# Power_Stage.net
KiCad netlist of a schematic drawn in Altium Designer
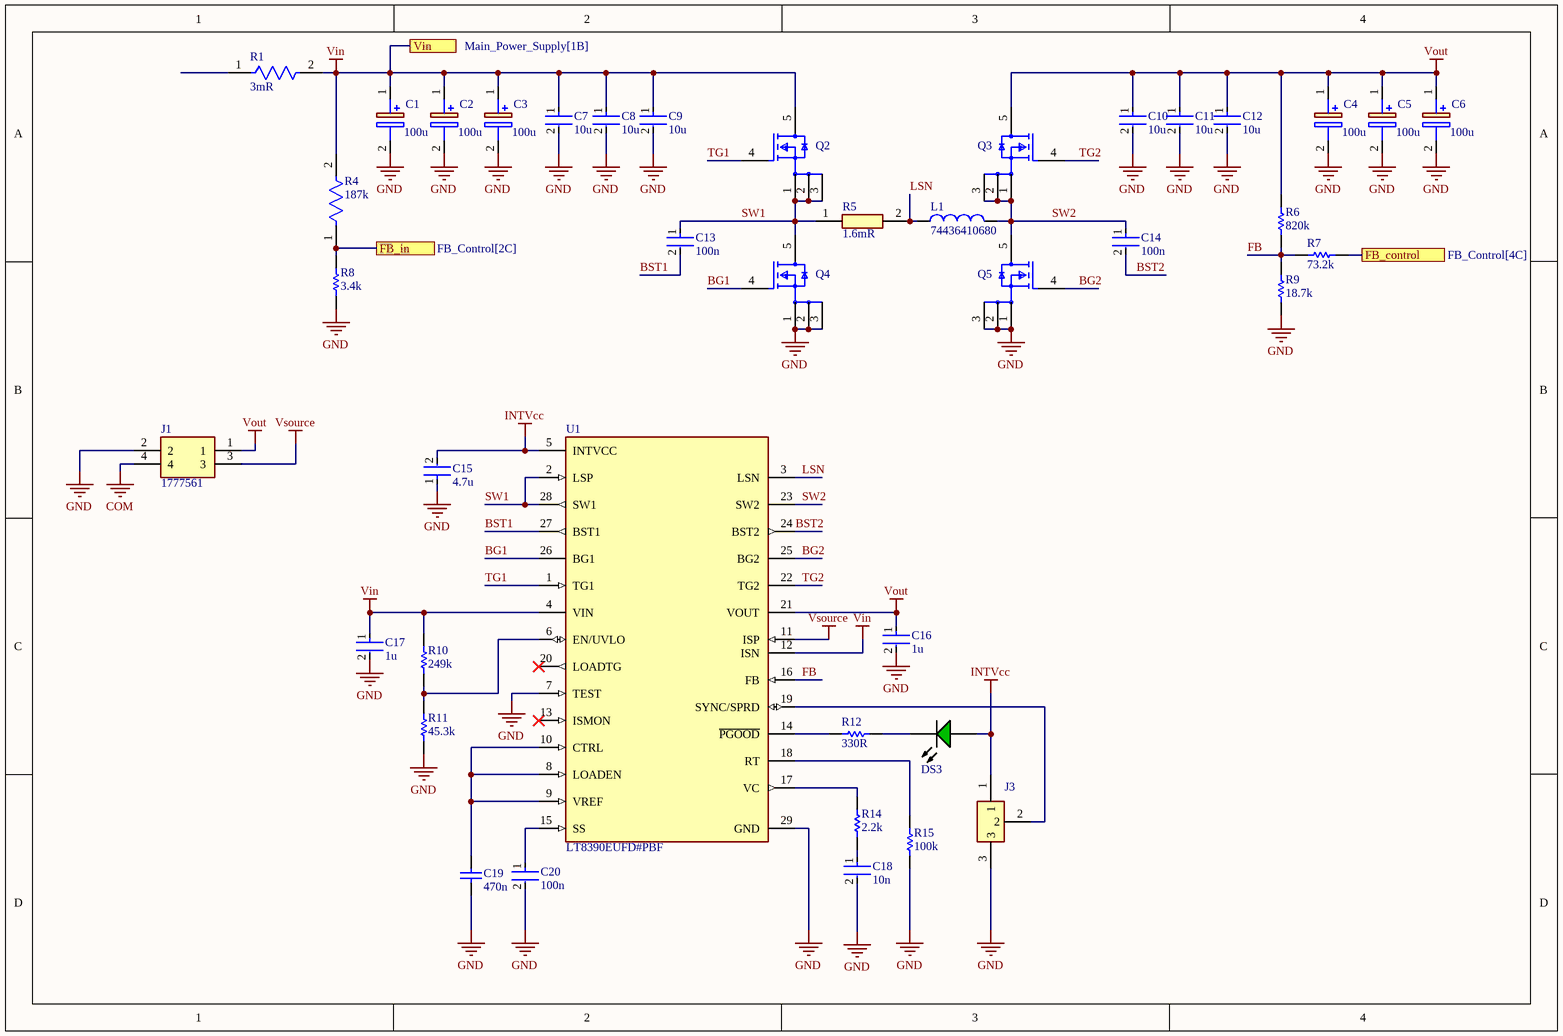
[diagram p0: Power_Stage.SchDoc]

(export (version "E")
  (design (tool "Eeschema 10.0.6"))
  (components
    (comp (ref "C1")
      (value "100u")
      (footprint "Library:CAPPRD500W65D1025H1700")
      (description "Aluminium Electrolytic Capacitors 100uF 100V - Radial Leaded Al Lytic Cap 85C Radial M Series")
      (fields
        (field (name "MANUFACTURER_PART_NUMBER") "ECA-2AM101B")
        (field (name "MOUSER PART NUMBER") "667-ECA-2AM101B")
      )
      (libsource (lib "*") (part "ECA-2AM101B"))
    )
    (comp (ref "C2")
      (value "100u")
      (footprint "Library:CAPPRD500W65D1025H1700")
      (description "Aluminium Electrolytic Capacitors 100uF 100V - Radial Leaded Al Lytic Cap 85C Radial M Series")
      (fields
        (field (name "MANUFACTURER_PART_NUMBER") "ECA-2AM101B")
        (field (name "MOUSER PART NUMBER") "667-ECA-2AM101B")
      )
      (libsource (lib "*") (part "ECA-2AM101B"))
    )
    (comp (ref "C3")
      (value "100u")
      (footprint "Library:CAPPRD500W65D1025H1700")
      (description "Aluminium Electrolytic Capacitors 100uF 100V - Radial Leaded Al Lytic Cap 85C Radial M Series")
      (fields
        (field (name "MANUFACTURER_PART_NUMBER") "ECA-2AM101B")
        (field (name "MOUSER PART NUMBER") "667-ECA-2AM101B")
      )
      (libsource (lib "*") (part "ECA-2AM101B"))
    )
    (comp (ref "C4")
      (value "100u")
      (footprint "Library:CAPPRD500W65D1025H1700")
      (description "Aluminium Electrolytic Capacitors 100uF 100V - Radial Leaded Al Lytic Cap 85C Radial M Series")
      (fields
        (field (name "MANUFACTURER_PART_NUMBER") "ECA-2AM101B")
        (field (name "MOUSER PART NUMBER") "667-ECA-2AM101B")
      )
      (libsource (lib "*") (part "ECA-2AM101B"))
    )
    (comp (ref "C5")
      (value "100u")
      (footprint "Library:CAPPRD500W65D1025H1700")
      (description "Aluminium Electrolytic Capacitors 100uF 100V - Radial Leaded Al Lytic Cap 85C Radial M Series")
      (fields
        (field (name "MANUFACTURER_PART_NUMBER") "ECA-2AM101B")
        (field (name "MOUSER PART NUMBER") "667-ECA-2AM101B")
      )
      (libsource (lib "*") (part "ECA-2AM101B"))
    )
    (comp (ref "C6")
      (value "100u")
      (footprint "Library:CAPPRD500W65D1025H1700")
      (description "Aluminium Electrolytic Capacitors 100uF 100V - Radial Leaded Al Lytic Cap 85C Radial M Series")
      (fields
        (field (name "MANUFACTURER_PART_NUMBER") "ECA-2AM101B")
        (field (name "MOUSER PART NUMBER") "667-ECA-2AM101B")
      )
      (libsource (lib "*") (part "ECA-2AM101B"))
    )
    (comp (ref "C7")
      (value "10u")
      (footprint "FP-GRM32E-0_3-0_2-MFG")
      (description "Chip Multilayer Ceramic Capacitors for General Purpose, 1210, 10uF, X7S, 22%, 10%, 100V")
      (fields (field (name "TOLERANCE") "10%"))
      (libsource (lib "Altium Content Vault") (part "02cd4be3c70576c341d710602a673aa"))
    )
    (comp (ref "C8")
      (value "10u")
      (footprint "FP-GRM32E-0_3-0_2-MFG")
      (description "Chip Multilayer Ceramic Capacitors for General Purpose, 1210, 10uF, X7S, 22%, 10%, 100V")
      (fields (field (name "TOLERANCE") "10%"))
      (libsource (lib "Altium Content Vault") (part "02cd4be3c70576c341d710602a673aa"))
    )
    (comp (ref "C9")
      (value "10u")
      (footprint "FP-GRM32E-0_3-0_2-MFG")
      (description "Chip Multilayer Ceramic Capacitors for General Purpose, 1210, 10uF, X7S, 22%, 10%, 100V")
      (fields (field (name "TOLERANCE") "10%"))
      (libsource (lib "Altium Content Vault") (part "02cd4be3c70576c341d710602a673aa"))
    )
    (comp (ref "C10")
      (value "10u")
      (footprint "FP-GRM32E-0_3-0_2-MFG")
      (description "Chip Multilayer Ceramic Capacitors for General Purpose, 1210, 10uF, X7S, 22%, 10%, 100V")
      (fields (field (name "TOLERANCE") "10%"))
      (libsource (lib "Altium Content Vault") (part "02cd4be3c70576c341d710602a673aa"))
    )
    (comp (ref "C11")
      (value "10u")
      (footprint "FP-GRM32E-0_3-0_2-MFG")
      (description "Chip Multilayer Ceramic Capacitors for General Purpose, 1210, 10uF, X7S, 22%, 10%, 100V")
      (fields (field (name "TOLERANCE") "10%"))
      (libsource (lib "Altium Content Vault") (part "02cd4be3c70576c341d710602a673aa"))
    )
    (comp (ref "C12")
      (value "10u")
      (footprint "FP-GRM32E-0_3-0_2-MFG")
      (description "Chip Multilayer Ceramic Capacitors for General Purpose, 1210, 10uF, X7S, 22%, 10%, 100V")
      (fields (field (name "TOLERANCE") "10%"))
      (libsource (lib "Altium Content Vault") (part "02cd4be3c70576c341d710602a673aa"))
    )
    (comp (ref "C13")
      (value "100n")
      (footprint "FP-0805-L_2_01_0_2-W_1_25-MFG")
      (description "General Purpose Ceramic Capacitor, 0805, 100nF, 5%, X7R, 0.15, 50V")
      (fields (field (name "TOLERANCE") "5%") (field (name "VOLTAGE") "50V"))
      (libsource (lib "Altium Content Vault") (part "02cd4be3c70576c341d710602a673aa"))
    )
    (comp (ref "C14")
      (value "100n")
      (footprint "FP-0805-L_2_01_0_2-W_1_25-MFG")
      (description "General Purpose Ceramic Capacitor, 0805, 100nF, 5%, X7R, 0.15, 50V")
      (fields (field (name "TOLERANCE") "5%") (field (name "VOLTAGE") "50V"))
      (libsource (lib "Altium Content Vault") (part "02cd4be3c70576c341d710602a673aa"))
    )
    (comp (ref "C15")
      (value "4.7u")
      (footprint "FP-0805-L_2_01_0_2-W_1_25-IPC_A")
      (description "General Purpose Ceramic Capacitor, 0805, 4.7uF, 10%, X5R, 0.15, 10V")
      (fields (field (name "VOLTAGE") "10V") (field (name "TOLERANCE") "10%"))
      (libsource (lib "Altium Content Vault") (part "02cd4be3c70576c341d710602a673aa"))
    )
    (comp (ref "C16")
      (value "1u")
      (footprint "FP-1210-L_3_3_0_4-W_2_5_0-IPC_C")
      (description "General Purpose Ceramic Capacitor, 1210, 1uF, 10%, X7R, 15%, 100V")
      (fields (field (name "TOLERANCE") "20%") (field (name "VOLTAGE") "100V"))
      (libsource (lib "Altium Content Vault") (part "b4654b650e69147ec39a6b967a45e02"))
    )
    (comp (ref "C17")
      (value "1u")
      (footprint "FP-1210-L_3_3_0_4-W_2_5_0-IPC_C")
      (description "General Purpose Ceramic Capacitor, 1210, 1uF, 10%, X7R, 15%, 100V")
      (fields (field (name "TOLERANCE") "20%") (field (name "VOLTAGE") "100V"))
      (libsource (lib "Altium Content Vault") (part "b4654b650e69147ec39a6b967a45e02"))
    )
    (comp (ref "C18")
      (value "10n")
      (footprint "FP-0805-L_2_01_0_2-W_1_25-IPC_B")
      (description "General Purpose Ceramic Capacitor, 0805, 10nF, 5%, X7R, 0.15, 50V")
      (fields (field (name "VOLTAGE") "50V") (field (name "TOLERANCE") "5%"))
      (libsource (lib "Altium Content Vault") (part "02cd4be3c70576c341d710602a673aa"))
    )
    (comp (ref "C19")
      (value "470n")
      (footprint "CAPC2013X140X50ML20T25")
      (fields
        (field (name "MANUFACTURER") "AVX Interconnect / Elco")
        (field (name "PART NUMBER") "08055C474JAT2A")
      )
      (libsource (lib "Altium Content Vault") (part "CAP"))
    )
    (comp (ref "C20")
      (value "100n")
      (footprint "FP-0805-L_2_01_0_2-W_1_25-MFG")
      (description "General Purpose Ceramic Capacitor, 0805, 100nF, 5%, X7R, 0.15, 50V")
      (fields (field (name "TOLERANCE") "5%") (field (name "VOLTAGE") "50V"))
      (libsource (lib "Altium Content Vault") (part "02cd4be3c70576c341d710602a673aa"))
    )
    (comp (ref "DS3")
      (value "LTST-C170KGKT")
      (footprint "LTST-LTST-C170KGKT-2_V")
      (description "Ultra Bright AlInGaP Chip LED, 75 mW, -55 to 85 degC, 2-Pin SMD (0805), RoHS, Tape and Reel")
      (fields (field (name "MANUFACTURER") "Lite-On"))
      (libsource (lib "Altium Content Vault") (part "LED-GREEN-KA-2"))
    )
    (comp (ref "J1")
      (value "1777561")
      (footprint "Library:1777561")
      (description "Connector")
      (fields (field (name "MOUSER PART NUMBER") "651-1777561"))
      (libsource (lib "Library") (part "1777561"))
    )
    (comp (ref "J3")
      (value "22-28-4030")
      (footprint "Library:MOLEX_22-28-4030")
      (description "Connector Header Through Hole 3 position 0.100\" (2.54mm)")
      (libsource (lib "Library") (part "22-28-4030"))
    )
    (comp (ref "L1")
      (value "74436410680")
      (footprint "WE-HCF_2815")
      (description "74436410680 Inductor, high current, 6.8uH, 1.44mOhm, 27mmL x 28mmW x 15.4mmH, SMT")
      (libsource (lib "Altium Content Vault") (part "Inductor - 1"))
    )
    (comp (ref "Q2")
      (value "NVMYS3D3N06CLTWG")
      (footprint "FP-760AB-MFG")
      (description "NVMYS3D3N06CLTWG Single Mosfet Transistors Rohs Compliant: Yes")
      (libsource (lib "Altium Content Vault") (part "47be8b74c5e268e5f463571878acc0e"))
    )
    (comp (ref "Q3")
      (value "NVMYS3D3N06CLTWG")
      (footprint "FP-760AB-MFG")
      (description "NVMYS3D3N06CLTWG Single Mosfet Transistors Rohs Compliant: Yes")
      (libsource (lib "Altium Content Vault") (part "47be8b74c5e268e5f463571878acc0e"))
    )
    (comp (ref "Q4")
      (value "NVMYS3D3N06CLTWG")
      (footprint "FP-760AB-MFG")
      (description "NVMYS3D3N06CLTWG Single Mosfet Transistors Rohs Compliant: Yes")
      (libsource (lib "Altium Content Vault") (part "47be8b74c5e268e5f463571878acc0e"))
    )
    (comp (ref "Q5")
      (value "NVMYS3D3N06CLTWG")
      (footprint "FP-760AB-MFG")
      (description "NVMYS3D3N06CLTWG Single Mosfet Transistors Rohs Compliant: Yes")
      (libsource (lib "Altium Content Vault") (part "47be8b74c5e268e5f463571878acc0e"))
    )
    (comp (ref "R1")
      (value "3mR")
      (footprint "FP-CSS2H-3920K-3L00FE-MFG")
      (description "RES 0.003 OHM 1% 5W 3920")
      (fields (field (name "TOLERANCE") "1%"))
      (libsource (lib "Altium Content Vault") (part "1029c3af85768c4190bb7ad29bc67b5"))
    )
    (comp (ref "R4")
      (value "187k")
      (footprint "FP-ERJ3EK-MFG")
      (description "RES SMD 187K OHM 1% 1/10W 0603")
      (fields (field (name "TOLERANCE") "1%"))
      (libsource (lib "Altium Content Vault") (part "1029c3af85768c4190bb7ad29bc67b5"))
    )
    (comp (ref "R5")
      (value "1.6mR")
      (footprint "Library:RESC6432X89N")
      (description "Current Sense Resistors - SMD 3watt .0016ohm 1%")
      (fields (field (name "MANUFACTURER_PART_NUMBER") "WSLP25121L600FEA"))
      (libsource (lib "*") (part "WSLP25121L600FEA"))
    )
    (comp (ref "R6")
      (value "820k")
      (footprint "RESC1608X55X30ML15T15")
      (fields (field (name "MANUFACTURER") "Panasonic") (field (name "PART NUMBER") "ERJ3EKF8203V"))
      (libsource (lib "Altium Content Vault") (part "RES"))
    )
    (comp (ref "R7")
      (value "73.2k")
      (footprint "RESC1005X40X25LL05T05")
      (fields (field (name "PART NUMBER") "ERJ-2RKF7322X") (field (name "MANUFACTURER") "Panasonic"))
      (libsource (lib "Altium Content Vault") (part "RES"))
    )
    (comp (ref "R8")
      (value "3.4k")
      (footprint "RESC1608X55X30LL15T15")
      (fields (field (name "PART NUMBER") "ERJ-3EKF3401V") (field (name "MANUFACTURER") "Panasonic"))
      (libsource (lib "Altium Content Vault") (part "RES"))
    )
    (comp (ref "R9")
      (value "18.7k")
      (footprint "RESC1608X55X30LL15T15")
      (fields (field (name "PART NUMBER") "ERJ-3EKF1872V") (field (name "MANUFACTURER") "Panasonic"))
      (libsource (lib "Altium Content Vault") (part "RES"))
    )
    (comp (ref "R10")
      (value "249k")
      (footprint "RESC1608X55X30ML15T15")
      (fields (field (name "PART NUMBER") "ERJ-3EKF2493V") (field (name "MANUFACTURER") "Panasonic"))
      (libsource (lib "Altium Content Vault") (part "RES"))
    )
    (comp (ref "R11")
      (value "45.3k")
      (footprint "RESC1608X55X30ML15T15")
      (fields (field (name "MANUFACTURER") "Panasonic") (field (name "PART NUMBER") "ERJ-3EKF4532V"))
      (libsource (lib "Altium Content Vault") (part "RES"))
    )
    (comp (ref "R12")
      (value "330R")
      (footprint "RESC1608X55X30LL15T15")
      (description "Chip Resistor, 330 Ohm, +/- 1%, 0.1 W, -55 to 155 degC, 0603 (1608 Metric), RoHS, Tape and Reel")
      (libsource (lib "Altium Content Vault") (part "RES-2"))
    )
    (comp (ref "R14")
      (value "2.2k")
      (footprint "RESC1608X55X30LL15T15")
      (fields (field (name "PART NUMBER") "ERJ3EKF2201V") (field (name "MANUFACTURER") "Panasonic"))
      (libsource (lib "Altium Content Vault") (part "RES"))
    )
    (comp (ref "R15")
      (value "100k")
      (footprint "RESC1608X55X30ML15T15")
      (fields (field (name "PART NUMBER") "ERJ-3EKF1003V") (field (name "MANUFACTURER") "Panasonic"))
      (libsource (lib "Altium Content Vault") (part "RES"))
    )
    (comp (ref "U1")
      (value "LT8390EUFD#PBF")
      (footprint "FP-UFD-28-05-08-1712-MFG")
      (description "IC REG CTRLR BUCK/BOOST 28QFN")
      (libsource (lib "Altium Content Vault") (part "bdcd0505c8727e03998dc9dfa31625b"))
    )
  )
  (nets
    (net (code "1") (name "/BG1") (class "Default")
      (node (ref "Q4") (pin "4") (pinfunction "G_4") (pintype "passive"))
      (node (ref "U1") (pin "26") (pinfunction "BG1_26") (pintype "passive"))
    )
    (net (code "2") (name "/BG2") (class "Default")
      (node (ref "Q5") (pin "4") (pinfunction "G_4") (pintype "passive"))
      (node (ref "U1") (pin "25") (pinfunction "BG2_25") (pintype "passive"))
    )
    (net (code "3") (name "/BST1") (class "Default")
      (node (ref "C13") (pin "2") (pinfunction "2_2") (pintype "passive"))
      (node (ref "U1") (pin "27") (pinfunction "BST1_27") (pintype "output"))
    )
    (net (code "4") (name "/BST2") (class "Default")
      (node (ref "C14") (pin "2") (pinfunction "2_2") (pintype "passive"))
      (node (ref "U1") (pin "24") (pinfunction "BST2_24") (pintype "output"))
    )
    (net (code "5") (name "/FB") (class "Default")
      (node (ref "R6") (pin "1") (pinfunction "1_1") (pintype "passive"))
      (node (ref "R7") (pin "1") (pinfunction "1_1") (pintype "passive"))
      (node (ref "R9") (pin "2") (pinfunction "2_2") (pintype "passive"))
      (node (ref "U1") (pin "16") (pinfunction "FB_16") (pintype "input"))
    )
    (net (code "6") (name "/FB_control") (class "Default")
      (node (ref "R7") (pin "2") (pinfunction "2_2") (pintype "passive"))
    )
    (net (code "7") (name "/FB_in") (class "Default")
      (node (ref "R4") (pin "1") (pinfunction "1_1") (pintype "passive"))
      (node (ref "R8") (pin "2") (pinfunction "2_2") (pintype "passive"))
    )
    (net (code "8") (name "/LSN") (class "Default")
      (node (ref "L1") (pin "1") (pinfunction "1_1") (pintype "passive"))
      (node (ref "R5") (pin "2") (pinfunction "2_2") (pintype "passive"))
      (node (ref "U1") (pin "3") (pinfunction "LSN_3") (pintype "power_in"))
    )
    (net (code "9") (name "/SW1") (class "Default")
      (node (ref "C13") (pin "1") (pinfunction "1_1") (pintype "passive"))
      (node (ref "Q2") (pin "1") (pinfunction "S_1") (pintype "passive"))
      (node (ref "Q2") (pin "2") (pinfunction "S_2") (pintype "passive"))
      (node (ref "Q2") (pin "3") (pinfunction "S_3") (pintype "passive"))
      (node (ref "Q4") (pin "5") (pinfunction "D_5") (pintype "passive"))
      (node (ref "R5") (pin "1") (pinfunction "1_1") (pintype "passive"))
      (node (ref "U1") (pin "2") (pinfunction "LSP_2") (pintype "input"))
      (node (ref "U1") (pin "28") (pinfunction "SW1_28") (pintype "output"))
    )
    (net (code "10") (name "/SW2") (class "Default")
      (node (ref "C14") (pin "1") (pinfunction "1_1") (pintype "passive"))
      (node (ref "L1") (pin "2") (pinfunction "2_2") (pintype "passive"))
      (node (ref "Q3") (pin "1") (pinfunction "S_1") (pintype "passive"))
      (node (ref "Q3") (pin "2") (pinfunction "S_2") (pintype "passive"))
      (node (ref "Q3") (pin "3") (pinfunction "S_3") (pintype "passive"))
      (node (ref "Q5") (pin "5") (pinfunction "D_5") (pintype "passive"))
      (node (ref "U1") (pin "23") (pinfunction "SW2_23") (pintype "open_collector"))
    )
    (net (code "11") (name "/TG1") (class "Default")
      (node (ref "Q2") (pin "4") (pinfunction "G_4") (pintype "passive"))
      (node (ref "U1") (pin "1") (pinfunction "TG1_1") (pintype "input"))
    )
    (net (code "12") (name "/TG2") (class "Default")
      (node (ref "Q3") (pin "4") (pinfunction "G_4") (pintype "passive"))
      (node (ref "U1") (pin "22") (pinfunction "TG2_22") (pintype "passive"))
    )
    (net (code "13") (name "COM") (class "Default")
      (node (ref "J1") (pin "4") (pinfunction "4_4") (pintype "passive"))
    )
    (net (code "14") (name "GND") (class "Default")
      (node (ref "C1") (pin "2") (pinfunction "-_2") (pintype "passive"))
      (node (ref "C10") (pin "2") (pinfunction "2_2") (pintype "passive"))
      (node (ref "C11") (pin "2") (pinfunction "2_2") (pintype "passive"))
      (node (ref "C12") (pin "2") (pinfunction "2_2") (pintype "passive"))
      (node (ref "C15") (pin "1") (pinfunction "1_1") (pintype "passive"))
      (node (ref "C16") (pin "2") (pinfunction "2_2") (pintype "passive"))
      (node (ref "C17") (pin "2") (pinfunction "2_2") (pintype "passive"))
      (node (ref "C18") (pin "2") (pinfunction "2_2") (pintype "passive"))
      (node (ref "C19") (pin "1") (pinfunction "1_1") (pintype "passive"))
      (node (ref "C2") (pin "2") (pinfunction "-_2") (pintype "passive"))
      (node (ref "C20") (pin "2") (pinfunction "2_2") (pintype "passive"))
      (node (ref "C3") (pin "2") (pinfunction "-_2") (pintype "passive"))
      (node (ref "C4") (pin "2") (pinfunction "-_2") (pintype "passive"))
      (node (ref "C5") (pin "2") (pinfunction "-_2") (pintype "passive"))
      (node (ref "C6") (pin "2") (pinfunction "-_2") (pintype "passive"))
      (node (ref "C7") (pin "2") (pinfunction "2_2") (pintype "passive"))
      (node (ref "C8") (pin "2") (pinfunction "2_2") (pintype "passive"))
      (node (ref "C9") (pin "2") (pinfunction "2_2") (pintype "passive"))
      (node (ref "J1") (pin "2") (pinfunction "2_2") (pintype "passive"))
      (node (ref "J3") (pin "3") (pinfunction "3_3") (pintype "passive"))
      (node (ref "Q4") (pin "1") (pinfunction "S_1") (pintype "passive"))
      (node (ref "Q4") (pin "2") (pinfunction "S_2") (pintype "passive"))
      (node (ref "Q4") (pin "3") (pinfunction "S_3") (pintype "passive"))
      (node (ref "Q5") (pin "1") (pinfunction "S_1") (pintype "passive"))
      (node (ref "Q5") (pin "2") (pinfunction "S_2") (pintype "passive"))
      (node (ref "Q5") (pin "3") (pinfunction "S_3") (pintype "passive"))
      (node (ref "R11") (pin "1") (pinfunction "1_1") (pintype "passive"))
      (node (ref "R15") (pin "2") (pinfunction "2_2") (pintype "passive"))
      (node (ref "R8") (pin "1") (pinfunction "1_1") (pintype "passive"))
      (node (ref "R9") (pin "1") (pinfunction "1_1") (pintype "passive"))
      (node (ref "U1") (pin "29") (pinfunction "GND_29") (pintype "power_in"))
      (node (ref "U1") (pin "7") (pinfunction "TEST_7") (pintype "input"))
    )
    (net (code "15") (name "INTVcc") (class "Default")
      (node (ref "C15") (pin "2") (pinfunction "2_2") (pintype "passive"))
      (node (ref "DS3") (pin "2") (pinfunction "A_2") (pintype "passive"))
      (node (ref "J3") (pin "1") (pinfunction "1_1") (pintype "passive"))
      (node (ref "U1") (pin "5") (pinfunction "INTVCC_5") (pintype "power_in"))
    )
    (net (code "16") (name "Net-(C18-Pad1)") (class "Default")
      (node (ref "C18") (pin "1") (pinfunction "1_1") (pintype "passive"))
      (node (ref "R14") (pin "1") (pinfunction "1_1") (pintype "passive"))
    )
    (net (code "17") (name "Net-(DS3-K)") (class "Default")
      (node (ref "DS3") (pin "1") (pinfunction "K_1") (pintype "passive"))
      (node (ref "R12") (pin "1") (pinfunction "1_1") (pintype "passive"))
    )
    (net (code "18") (name "Net-(U1-CTRL)") (class "Default")
      (node (ref "C19") (pin "2") (pinfunction "2_2") (pintype "passive"))
      (node (ref "U1") (pin "10") (pinfunction "CTRL_10") (pintype "input"))
      (node (ref "U1") (pin "8") (pinfunction "LOADEN_8") (pintype "input"))
      (node (ref "U1") (pin "9") (pinfunction "VREF_9") (pintype "input"))
    )
    (net (code "19") (name "Net-(U1-EN{slash}UVLO)") (class "Default")
      (node (ref "R10") (pin "1") (pinfunction "1_1") (pintype "passive"))
      (node (ref "R11") (pin "2") (pinfunction "2_2") (pintype "passive"))
      (node (ref "U1") (pin "6") (pinfunction "EN/UVLO_6") (pintype "bidirectional"))
    )
    (net (code "20") (name "Net-(U1-RT)") (class "Default")
      (node (ref "R15") (pin "1") (pinfunction "1_1") (pintype "passive"))
      (node (ref "U1") (pin "18") (pinfunction "RT_18") (pintype "passive"))
    )
    (net (code "21") (name "Net-(U1-SS)") (class "Default")
      (node (ref "C20") (pin "1") (pinfunction "1_1") (pintype "passive"))
      (node (ref "U1") (pin "15") (pinfunction "SS_15") (pintype "input"))
    )
    (net (code "22") (name "Net-(U1-SYNC{slash}SPRD)") (class "Default")
      (node (ref "J3") (pin "2") (pinfunction "2_2") (pintype "passive"))
      (node (ref "U1") (pin "19") (pinfunction "SYNC/SPRD_19") (pintype "bidirectional"))
    )
    (net (code "23") (name "Net-(U1-VC)") (class "Default")
      (node (ref "R14") (pin "2") (pinfunction "2_2") (pintype "passive"))
      (node (ref "U1") (pin "17") (pinfunction "VC_17") (pintype "output"))
    )
    (net (code "24") (name "Net-(U1-~{PGOOD})") (class "Default")
      (node (ref "R12") (pin "2") (pinfunction "2_2") (pintype "passive"))
      (node (ref "U1") (pin "14") (pinfunction "~{PGOOD}_14") (pintype "open_collector"))
    )
    (net (code "25") (name "Vin") (class "Default")
      (node (ref "C1") (pin "1") (pinfunction "+_1") (pintype "passive"))
      (node (ref "C17") (pin "1") (pinfunction "1_1") (pintype "passive"))
      (node (ref "C2") (pin "1") (pinfunction "+_1") (pintype "passive"))
      (node (ref "C3") (pin "1") (pinfunction "+_1") (pintype "passive"))
      (node (ref "C7") (pin "1") (pinfunction "1_1") (pintype "passive"))
      (node (ref "C8") (pin "1") (pinfunction "1_1") (pintype "passive"))
      (node (ref "C9") (pin "1") (pinfunction "1_1") (pintype "passive"))
      (node (ref "Q2") (pin "5") (pinfunction "D_5") (pintype "passive"))
      (node (ref "R1") (pin "2") (pinfunction "2_2") (pintype "passive"))
      (node (ref "R10") (pin "2") (pinfunction "2_2") (pintype "passive"))
      (node (ref "R4") (pin "2") (pinfunction "2_2") (pintype "passive"))
      (node (ref "U1") (pin "12") (pinfunction "ISN_12") (pintype "power_in"))
      (node (ref "U1") (pin "4") (pinfunction "VIN_4") (pintype "power_in"))
    )
    (net (code "26") (name "Vout") (class "Default")
      (node (ref "C10") (pin "1") (pinfunction "1_1") (pintype "passive"))
      (node (ref "C11") (pin "1") (pinfunction "1_1") (pintype "passive"))
      (node (ref "C12") (pin "1") (pinfunction "1_1") (pintype "passive"))
      (node (ref "C16") (pin "1") (pinfunction "1_1") (pintype "passive"))
      (node (ref "C4") (pin "1") (pinfunction "+_1") (pintype "passive"))
      (node (ref "C5") (pin "1") (pinfunction "+_1") (pintype "passive"))
      (node (ref "C6") (pin "1") (pinfunction "+_1") (pintype "passive"))
      (node (ref "J1") (pin "1") (pinfunction "1_1") (pintype "passive"))
      (node (ref "Q3") (pin "5") (pinfunction "D_5") (pintype "passive"))
      (node (ref "R6") (pin "2") (pinfunction "2_2") (pintype "passive"))
      (node (ref "U1") (pin "21") (pinfunction "VOUT_21") (pintype "open_collector"))
    )
    (net (code "27") (name "Vsource") (class "Default")
      (node (ref "J1") (pin "3") (pinfunction "3_3") (pintype "passive"))
      (node (ref "U1") (pin "11") (pinfunction "ISP_11") (pintype "input"))
    )
    (net (code "28") (name "unconnected-(R1-Pad1)") (class "Default")
      (node (ref "R1") (pin "1") (pinfunction "1_1") (pintype "passive"))
    )
    (net (code "29") (name "unconnected-(U1-ISMON-Pad13)") (class "Default")
      (node (ref "U1") (pin "13") (pinfunction "ISMON_13") (pintype "input+no_connect"))
    )
    (net (code "30") (name "unconnected-(U1-LOADTG-Pad20)") (class "Default")
      (node (ref "U1") (pin "20") (pinfunction "LOADTG_20") (pintype "output+no_connect"))
    )
  )
)
